# Docking_Connection.net
KiCad netlist of a schematic drawn in Altium Designer
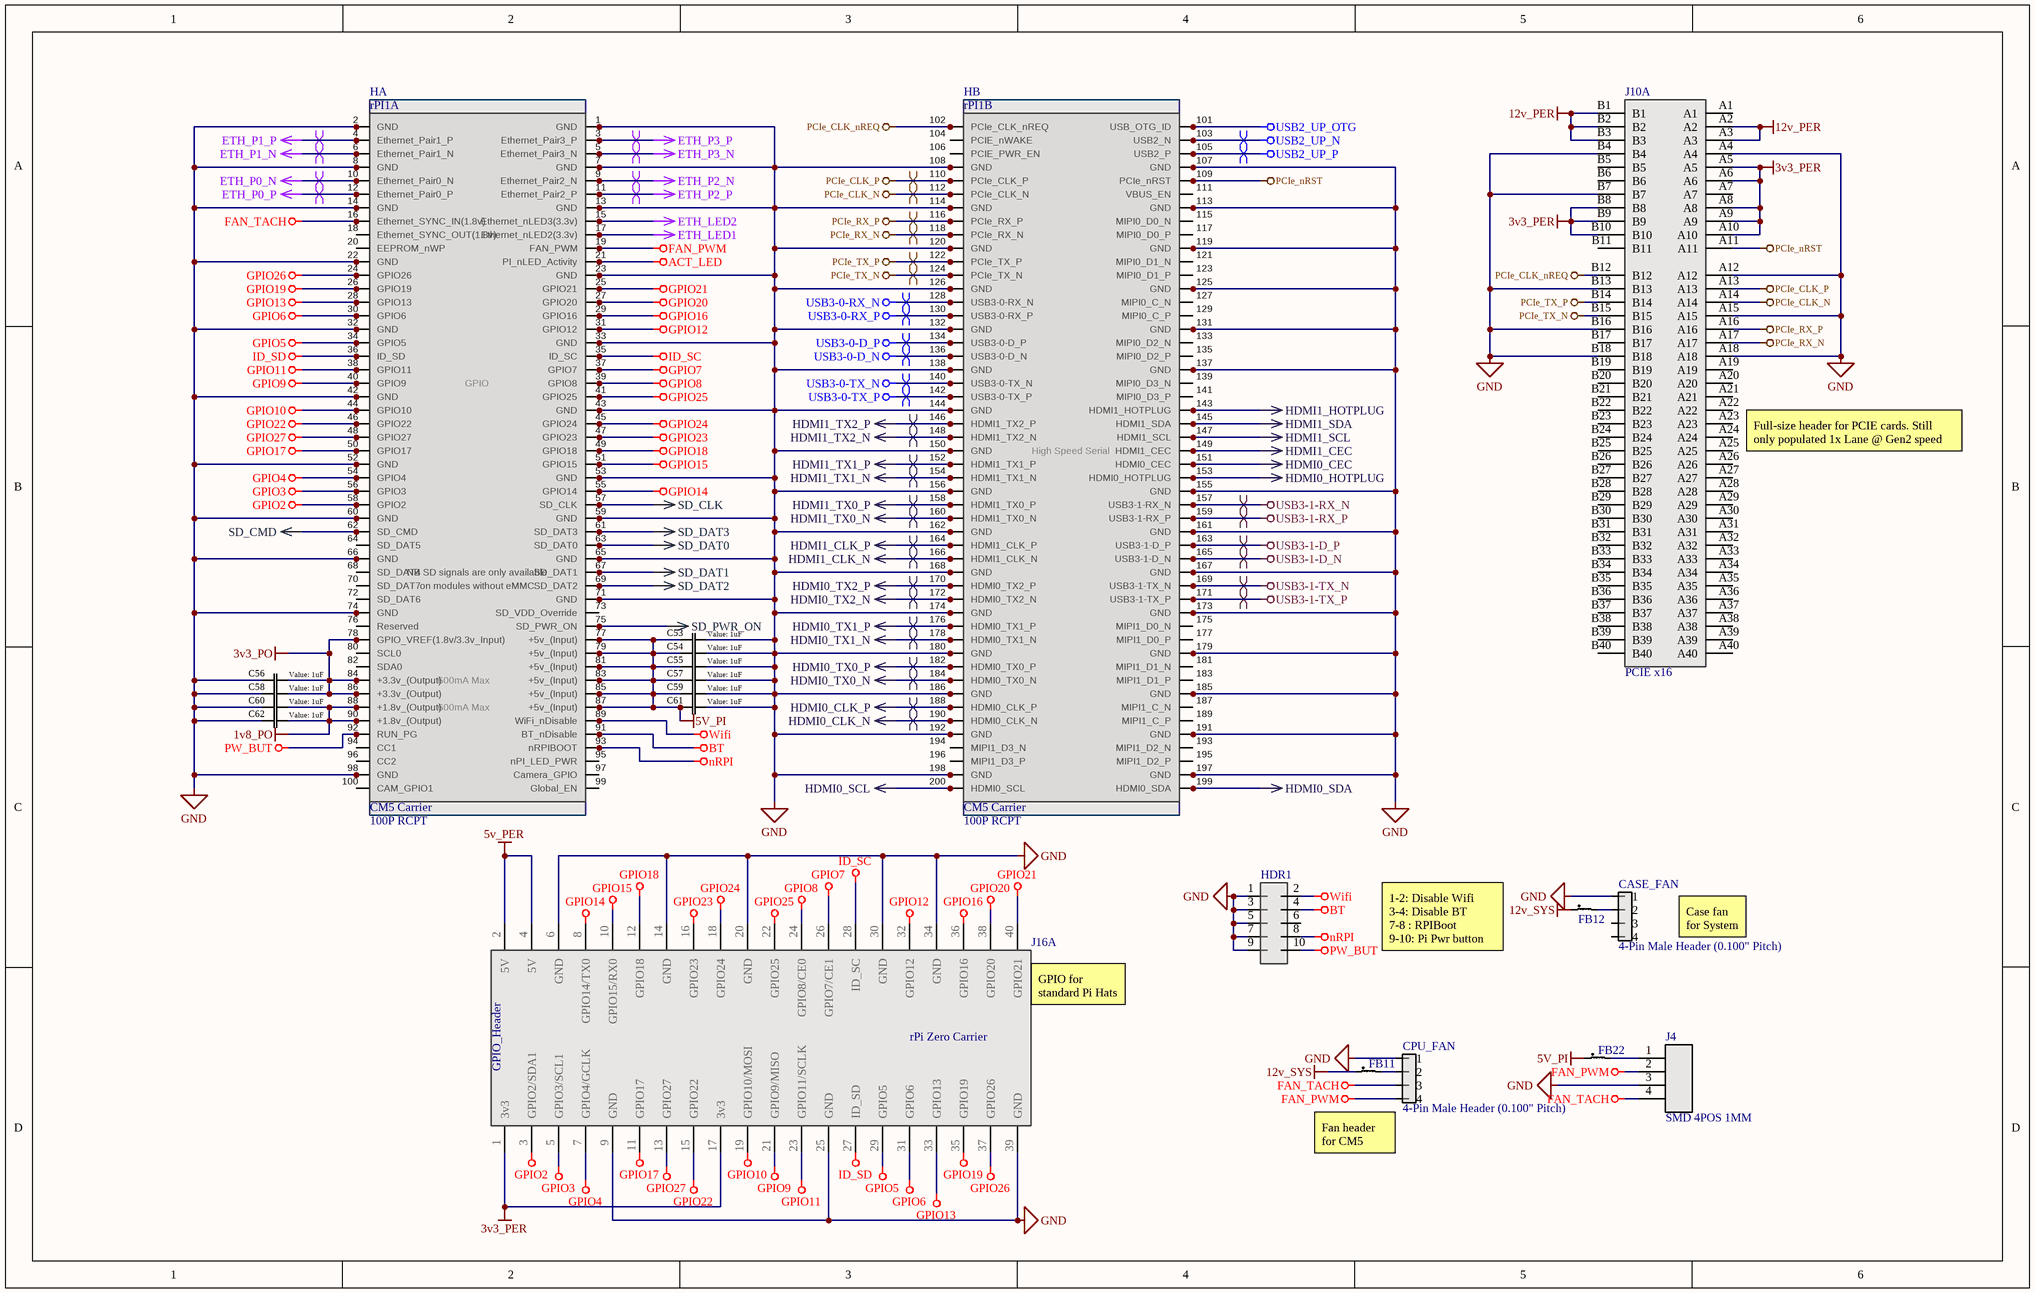
[diagram p0: Docking_Connection.SchDoc]

(export (version "E")
  (design (tool "Eeschema 10.0.6"))
  (components
    (comp (ref "C53")
      (value "1uF")
      (footprint "0603")
      (fields
        (field (name "VOLTAGE") "6V")
        (field (name "TOLERANCE") "5%")
        (field (name "Comment") "Generic Capacitor")
      )
      (libsource (lib "Capacitors") (part "Generic Capacitor"))
    )
    (comp (ref "C54")
      (value "1uF")
      (footprint "0603")
      (fields
        (field (name "VOLTAGE") "6V")
        (field (name "TOLERANCE") "5%")
        (field (name "Comment") "Generic Capacitor")
      )
      (libsource (lib "Capacitors") (part "Generic Capacitor"))
    )
    (comp (ref "C55")
      (value "1uF")
      (footprint "0603")
      (fields
        (field (name "VOLTAGE") "6V")
        (field (name "TOLERANCE") "5%")
        (field (name "Comment") "Generic Capacitor")
      )
      (libsource (lib "Capacitors") (part "Generic Capacitor"))
    )
    (comp (ref "C56")
      (value "1uF")
      (footprint "0603")
      (fields
        (field (name "VOLTAGE") "6V")
        (field (name "TOLERANCE") "5%")
        (field (name "Comment") "Generic Capacitor")
      )
      (libsource (lib "Capacitors") (part "Generic Capacitor"))
    )
    (comp (ref "C57")
      (value "1uF")
      (footprint "0603")
      (fields
        (field (name "VOLTAGE") "6V")
        (field (name "TOLERANCE") "5%")
        (field (name "Comment") "Generic Capacitor")
      )
      (libsource (lib "Capacitors") (part "Generic Capacitor"))
    )
    (comp (ref "C58")
      (value "1uF")
      (footprint "0603")
      (fields
        (field (name "VOLTAGE") "6V")
        (field (name "TOLERANCE") "5%")
        (field (name "Comment") "Generic Capacitor")
      )
      (libsource (lib "Capacitors") (part "Generic Capacitor"))
    )
    (comp (ref "C59")
      (value "1uF")
      (footprint "0603")
      (fields
        (field (name "VOLTAGE") "6V")
        (field (name "TOLERANCE") "5%")
        (field (name "Comment") "Generic Capacitor")
      )
      (libsource (lib "Capacitors") (part "Generic Capacitor"))
    )
    (comp (ref "C60")
      (value "1uF")
      (footprint "0603")
      (fields
        (field (name "VOLTAGE") "6V")
        (field (name "TOLERANCE") "5%")
        (field (name "Comment") "Generic Capacitor")
      )
      (libsource (lib "Capacitors") (part "Generic Capacitor"))
    )
    (comp (ref "C61")
      (value "1uF")
      (footprint "0603")
      (fields
        (field (name "VOLTAGE") "6V")
        (field (name "TOLERANCE") "5%")
        (field (name "Comment") "Generic Capacitor")
      )
      (libsource (lib "Capacitors") (part "Generic Capacitor"))
    )
    (comp (ref "C62")
      (value "1uF")
      (footprint "0603")
      (fields
        (field (name "VOLTAGE") "6V")
        (field (name "TOLERANCE") "5%")
        (field (name "Comment") "Generic Capacitor")
      )
      (libsource (lib "Capacitors") (part "Generic Capacitor"))
    )
    (comp (ref "CASE_FAN")
      (value "4-Pin Male Header (0.100\" Pitch)")
      (footprint "TSW-104-07-T-S")
      (description "Connector Header Through Hole 4 position 0.100\" (2.54mm)")
      (libsource (lib "Connectors") (part "TSW-104-07-T-S"))
    )
    (comp (ref "CPU_FAN")
      (value "4-Pin Male Header (0.100\" Pitch)")
      (footprint "TSW-104-07-T-S")
      (description "Connector Header Through Hole 4 position 0.100\" (2.54mm)")
      (libsource (lib "Connectors") (part "TSW-104-07-T-S"))
    )
    (comp (ref "FB11")
      (value "0603 Ferrite")
      (footprint "0603")
      (description "120 Ohms @ 100 MHz 1 Signal Line Ferrite Bead 0603 (1608 Metric) 500mA 180mOhm")
      (fields
        (field (name "MANUFACTURER") "Pulse")
        (field (name "MANUFACTURER PART NUMBER") "PE-0603FB121ST")
      )
      (libsource (lib "Inductors") (part "PE-0603FB121ST"))
    )
    (comp (ref "FB12")
      (value "0603 Ferrite")
      (footprint "0603")
      (description "120 Ohms @ 100 MHz 1 Signal Line Ferrite Bead 0603 (1608 Metric) 500mA 180mOhm")
      (fields
        (field (name "MANUFACTURER") "Pulse")
        (field (name "MANUFACTURER PART NUMBER") "PE-0603FB121ST")
      )
      (libsource (lib "Inductors") (part "PE-0603FB121ST"))
    )
    (comp (ref "FB22")
      (value "0603 Ferrite")
      (footprint "0603")
      (description "120 Ohms @ 100 MHz 1 Signal Line Ferrite Bead 0603 (1608 Metric) 500mA 180mOhm")
      (fields
        (field (name "MANUFACTURER") "Pulse")
        (field (name "MANUFACTURER PART NUMBER") "PE-0603FB121ST")
      )
      (libsource (lib "Inductors") (part "PE-0603FB121ST"))
    )
    (comp (ref "HA")
      (value "100P RCPT")
      (footprint "DF40HC(3.0)-100DS-0.4V(51)")
      (description "100 Position Connector Receptacle, Center Strip Contacts Surface Mount Gold")
      (fields (field (name "MF") "Hirose") (field (name "MP") "DF40C-100DS-0.4V(51)"))
      (libsource (lib "Connectors") (part "DF40-100DS RCPT_1"))
    )
    (comp (ref "HB")
      (value "100P RCPT")
      (footprint "DF40HC(3.0)-100DS-0.4V(51)")
      (description "100 Position Connector Receptacle, Center Strip Contacts Surface Mount Gold")
      (fields (field (name "MF") "Hirose") (field (name "MP") "DF40C-100DS-0.4V(51)"))
      (libsource (lib "Connectors") (part "DF40-100DS RCPT_1"))
    )
    (comp (ref "HDR1")
      (value "10pinMobo")
      (footprint "10pinMobo")
      (description "10pin motherboard jack")
      (libsource (lib "Connectors") (part "10pinMobo"))
    )
    (comp (ref "J4")
      (value "SMD 4POS 1MM")
      (footprint "CONN4_BM04B-SRSS_JST")
      (description "Connector Header Surface Mount 4 position 0.039\" (1.00mm)")
      (libsource (lib "Connectors") (part "BM04B-SRSS-TB"))
    )
    (comp (ref "J10")
      (value "PCIE x16")
      (footprint "10018783-10203TLF")
      (description "164 Position Female Connector PCI Express™ Gold 0.039\" (1.00mm) Black")
      (fields (field (name "MF") "Amphenol ICC") (field (name "MP") "10018783-10203TLF"))
      (libsource (lib "Connectors") (part "10018783-10203TLF"))
    )
    (comp (ref "J16")
      (value "rPi Zero Carrier")
      (footprint "rPiZero")
      (description "Raspberry Pi Zero/W/2W\r\nHeader, debug-pads, & mounting")
      (libsource (lib "SOC_Carrier") (part "RP-Zero"))
    )
    (comp (ref "rPI1")
      (value "CM5 Carrier")
      (footprint "CM4-FTPD")
      (description "Compute Module 5 Footprint\r\nOverlap Hirose 100P connector over pads to place actual components")
      (libsource (lib "Misc ICs") (part "RP-CM5"))
    )
  )
  (nets
    (net (code "1") (name "1v8_PO") (class "Default")
      (node (ref "C60") (pin "1") (pinfunction "1_1") (pintype "passive"))
      (node (ref "C62") (pin "1") (pinfunction "1_1") (pintype "passive"))
      (node (ref "HA") (pin "88") (pinfunction "88_88") (pintype "passive"))
      (node (ref "HA") (pin "90") (pinfunction "90_90") (pintype "passive"))
      (node (ref "rPI1") (pin "88") (pinfunction "+1.8v_(Output)_88") (pintype "passive"))
      (node (ref "rPI1") (pin "90") (pinfunction "+1.8v_(Output)_90") (pintype "passive"))
    )
    (net (code "2") (name "3v3_PER") (class "Default")
      (node (ref "J10") (pin "A10") (pinfunction "A10_A10") (pintype "passive"))
      (node (ref "J10") (pin "A5") (pinfunction "A5_A5") (pintype "passive"))
      (node (ref "J10") (pin "A6") (pinfunction "A6_A6") (pintype "passive"))
      (node (ref "J10") (pin "A8") (pinfunction "A8_A8") (pintype "passive"))
      (node (ref "J10") (pin "A9") (pinfunction "A9_A9") (pintype "passive"))
      (node (ref "J10") (pin "B10") (pinfunction "B10_B10") (pintype "passive"))
      (node (ref "J10") (pin "B8") (pinfunction "B8_B8") (pintype "passive"))
      (node (ref "J10") (pin "B9") (pinfunction "B9_B9") (pintype "passive"))
      (node (ref "J16") (pin "1") (pinfunction "3v3_1") (pintype "passive"))
      (node (ref "J16") (pin "17") (pinfunction "3v3_17") (pintype "passive"))
    )
    (net (code "3") (name "3v3_PO") (class "Default")
      (node (ref "C56") (pin "1") (pinfunction "1_1") (pintype "passive"))
      (node (ref "C58") (pin "1") (pinfunction "1_1") (pintype "passive"))
      (node (ref "HA") (pin "78") (pinfunction "78_78") (pintype "passive"))
      (node (ref "HA") (pin "84") (pinfunction "84_84") (pintype "passive"))
      (node (ref "HA") (pin "86") (pinfunction "86_86") (pintype "passive"))
      (node (ref "rPI1") (pin "78") (pinfunction "GPIO_VREF(1.8v/3.3v_Input)_78") (pintype "passive"))
      (node (ref "rPI1") (pin "84") (pinfunction "+3.3v_(Output)_84") (pintype "passive"))
      (node (ref "rPI1") (pin "86") (pinfunction "+3.3v_(Output)_86") (pintype "passive"))
    )
    (net (code "4") (name "5V_PI") (class "Default")
      (node (ref "C53") (pin "2") (pinfunction "2_2") (pintype "passive"))
      (node (ref "C54") (pin "2") (pinfunction "2_2") (pintype "passive"))
      (node (ref "C55") (pin "2") (pinfunction "2_2") (pintype "passive"))
      (node (ref "C57") (pin "2") (pinfunction "2_2") (pintype "passive"))
      (node (ref "C59") (pin "2") (pinfunction "2_2") (pintype "passive"))
      (node (ref "C61") (pin "2") (pinfunction "2_2") (pintype "passive"))
      (node (ref "FB22") (pin "1") (pinfunction "1_1") (pintype "passive"))
      (node (ref "HA") (pin "77") (pinfunction "77_77") (pintype "passive"))
      (node (ref "HA") (pin "79") (pinfunction "79_79") (pintype "passive"))
      (node (ref "HA") (pin "81") (pinfunction "81_81") (pintype "passive"))
      (node (ref "HA") (pin "83") (pinfunction "83_83") (pintype "passive"))
      (node (ref "HA") (pin "85") (pinfunction "85_85") (pintype "passive"))
      (node (ref "HA") (pin "87") (pinfunction "87_87") (pintype "passive"))
      (node (ref "rPI1") (pin "77") (pinfunction "+5v_(Input)_77") (pintype "passive"))
      (node (ref "rPI1") (pin "79") (pinfunction "+5v_(Input)_79") (pintype "passive"))
      (node (ref "rPI1") (pin "81") (pinfunction "+5v_(Input)_81") (pintype "passive"))
      (node (ref "rPI1") (pin "83") (pinfunction "+5v_(Input)_83") (pintype "passive"))
      (node (ref "rPI1") (pin "85") (pinfunction "+5v_(Input)_85") (pintype "passive"))
      (node (ref "rPI1") (pin "87") (pinfunction "+5v_(Input)_87") (pintype "passive"))
    )
    (net (code "5") (name "5v_PER") (class "Default")
      (node (ref "J16") (pin "2") (pinfunction "5V_2") (pintype "passive"))
      (node (ref "J16") (pin "4") (pinfunction "5V_4") (pintype "passive"))
    )
    (net (code "6") (name "12v_PER") (class "Default")
      (node (ref "J10") (pin "A2") (pinfunction "A2_A2") (pintype "passive"))
      (node (ref "J10") (pin "A3") (pinfunction "A3_A3") (pintype "passive"))
      (node (ref "J10") (pin "B1") (pinfunction "B1_B1") (pintype "passive"))
      (node (ref "J10") (pin "B2") (pinfunction "B2_B2") (pintype "passive"))
      (node (ref "J10") (pin "B3") (pinfunction "B3_B3") (pintype "passive"))
    )
    (net (code "7") (name "12v_SYS") (class "Default")
      (node (ref "FB11") (pin "1") (pinfunction "1_1") (pintype "passive"))
      (node (ref "FB12") (pin "1") (pinfunction "1_1") (pintype "passive"))
    )
    (net (code "8") (name "ACT_LED") (class "Default")
      (node (ref "HA") (pin "21") (pinfunction "21_21") (pintype "passive"))
      (node (ref "rPI1") (pin "21") (pinfunction "PI_nLED_Activity_21") (pintype "passive"))
    )
    (net (code "9") (name "BT") (class "Default")
      (node (ref "HA") (pin "91") (pinfunction "91_91") (pintype "passive"))
      (node (ref "HDR1") (pin "4") (pinfunction "4_4") (pintype "passive"))
      (node (ref "rPI1") (pin "91") (pinfunction "BT_nDisable_91") (pintype "passive"))
    )
    (net (code "10") (name "ETH_LED1") (class "Default")
      (node (ref "HA") (pin "17") (pinfunction "17_17") (pintype "passive"))
      (node (ref "rPI1") (pin "17") (pinfunction "Ethernet_nLED2(3.3v)_17") (pintype "passive"))
    )
    (net (code "11") (name "ETH_LED2") (class "Default")
      (node (ref "HA") (pin "15") (pinfunction "15_15") (pintype "passive"))
      (node (ref "rPI1") (pin "15") (pinfunction "Ethernet_nLED3(3.3v)_15") (pintype "passive"))
    )
    (net (code "12") (name "ETH_P0_N") (class "Default")
      (node (ref "HA") (pin "10") (pinfunction "10_10") (pintype "passive"))
      (node (ref "rPI1") (pin "10") (pinfunction "Ethernet_Pair0_N_10") (pintype "passive"))
    )
    (net (code "13") (name "ETH_P0_P") (class "Default")
      (node (ref "HA") (pin "12") (pinfunction "12_12") (pintype "passive"))
      (node (ref "rPI1") (pin "12") (pinfunction "Ethernet_Pair0_P_12") (pintype "passive"))
    )
    (net (code "14") (name "ETH_P1_N") (class "Default")
      (node (ref "HA") (pin "6") (pinfunction "6_6") (pintype "passive"))
      (node (ref "rPI1") (pin "6") (pinfunction "Ethernet_Pair1_N_6") (pintype "passive"))
    )
    (net (code "15") (name "ETH_P1_P") (class "Default")
      (node (ref "HA") (pin "4") (pinfunction "4_4") (pintype "passive"))
      (node (ref "rPI1") (pin "4") (pinfunction "Ethernet_Pair1_P_4") (pintype "passive"))
    )
    (net (code "16") (name "ETH_P2_N") (class "Default")
      (node (ref "HA") (pin "9") (pinfunction "9_9") (pintype "passive"))
      (node (ref "rPI1") (pin "9") (pinfunction "Ethernet_Pair2_N_9") (pintype "passive"))
    )
    (net (code "17") (name "ETH_P2_P") (class "Default")
      (node (ref "HA") (pin "11") (pinfunction "11_11") (pintype "passive"))
      (node (ref "rPI1") (pin "11") (pinfunction "Ethernet_Pair2_P_11") (pintype "passive"))
    )
    (net (code "18") (name "ETH_P3_N") (class "Default")
      (node (ref "HA") (pin "5") (pinfunction "5_5") (pintype "passive"))
      (node (ref "rPI1") (pin "5") (pinfunction "Ethernet_Pair3_N_5") (pintype "passive"))
    )
    (net (code "19") (name "ETH_P3_P") (class "Default")
      (node (ref "HA") (pin "3") (pinfunction "3_3") (pintype "passive"))
      (node (ref "rPI1") (pin "3") (pinfunction "Ethernet_Pair3_P_3") (pintype "passive"))
    )
    (net (code "20") (name "FAN_PWM") (class "Default")
      (node (ref "CPU_FAN") (pin "4") (pinfunction "4_4") (pintype "passive"))
      (node (ref "HA") (pin "19") (pinfunction "19_19") (pintype "passive"))
      (node (ref "J4") (pin "2") (pinfunction "2_2") (pintype "passive"))
      (node (ref "rPI1") (pin "19") (pinfunction "FAN_PWM_19") (pintype "passive"))
    )
    (net (code "21") (name "FAN_TACH") (class "Default")
      (node (ref "CPU_FAN") (pin "3") (pinfunction "3_3") (pintype "passive"))
      (node (ref "HA") (pin "16") (pinfunction "16_16") (pintype "passive"))
      (node (ref "J4") (pin "4") (pinfunction "4_4") (pintype "passive"))
      (node (ref "rPI1") (pin "16") (pinfunction "Ethernet_SYNC_IN(1.8v)_16") (pintype "passive"))
    )
    (net (code "22") (name "GND") (class "Default")
      (node (ref "C53") (pin "1") (pinfunction "1_1") (pintype "passive"))
      (node (ref "C54") (pin "1") (pinfunction "1_1") (pintype "passive"))
      (node (ref "C55") (pin "1") (pinfunction "1_1") (pintype "passive"))
      (node (ref "C56") (pin "2") (pinfunction "2_2") (pintype "passive"))
      (node (ref "C57") (pin "1") (pinfunction "1_1") (pintype "passive"))
      (node (ref "C58") (pin "2") (pinfunction "2_2") (pintype "passive"))
      (node (ref "C59") (pin "1") (pinfunction "1_1") (pintype "passive"))
      (node (ref "C60") (pin "2") (pinfunction "2_2") (pintype "passive"))
      (node (ref "C61") (pin "1") (pinfunction "1_1") (pintype "passive"))
      (node (ref "C62") (pin "2") (pinfunction "2_2") (pintype "passive"))
      (node (ref "CASE_FAN") (pin "1") (pinfunction "1_1") (pintype "passive"))
      (node (ref "CPU_FAN") (pin "1") (pinfunction "1_1") (pintype "passive"))
      (node (ref "HA") (pin "1") (pinfunction "1_1") (pintype "passive"))
      (node (ref "HA") (pin "13") (pinfunction "13_13") (pintype "passive"))
      (node (ref "HA") (pin "14") (pinfunction "14_14") (pintype "passive"))
      (node (ref "HA") (pin "2") (pinfunction "2_2") (pintype "passive"))
      (node (ref "HA") (pin "22") (pinfunction "22_22") (pintype "passive"))
      (node (ref "HA") (pin "23") (pinfunction "23_23") (pintype "passive"))
      (node (ref "HA") (pin "32") (pinfunction "32_32") (pintype "passive"))
      (node (ref "HA") (pin "33") (pinfunction "33_33") (pintype "passive"))
      (node (ref "HA") (pin "42") (pinfunction "42_42") (pintype "passive"))
      (node (ref "HA") (pin "43") (pinfunction "43_43") (pintype "passive"))
      (node (ref "HA") (pin "52") (pinfunction "52_52") (pintype "passive"))
      (node (ref "HA") (pin "53") (pinfunction "53_53") (pintype "passive"))
      (node (ref "HA") (pin "59") (pinfunction "59_59") (pintype "passive"))
      (node (ref "HA") (pin "60") (pinfunction "60_60") (pintype "passive"))
      (node (ref "HA") (pin "65") (pinfunction "65_65") (pintype "passive"))
      (node (ref "HA") (pin "66") (pinfunction "66_66") (pintype "passive"))
      (node (ref "HA") (pin "7") (pinfunction "7_7") (pintype "passive"))
      (node (ref "HA") (pin "71") (pinfunction "71_71") (pintype "passive"))
      (node (ref "HA") (pin "74") (pinfunction "74_74") (pintype "passive"))
      (node (ref "HA") (pin "8") (pinfunction "8_8") (pintype "passive"))
      (node (ref "HA") (pin "98") (pinfunction "98_98") (pintype "passive"))
      (node (ref "HB") (pin "13") (pinfunction "13_13") (pintype "passive"))
      (node (ref "HB") (pin "14") (pinfunction "14_14") (pintype "passive"))
      (node (ref "HB") (pin "19") (pinfunction "19_19") (pintype "passive"))
      (node (ref "HB") (pin "20") (pinfunction "20_20") (pintype "passive"))
      (node (ref "HB") (pin "25") (pinfunction "25_25") (pintype "passive"))
      (node (ref "HB") (pin "26") (pinfunction "26_26") (pintype "passive"))
      (node (ref "HB") (pin "31") (pinfunction "31_31") (pintype "passive"))
      (node (ref "HB") (pin "32") (pinfunction "32_32") (pintype "passive"))
      (node (ref "HB") (pin "37") (pinfunction "37_37") (pintype "passive"))
      (node (ref "HB") (pin "38") (pinfunction "38_38") (pintype "passive"))
      (node (ref "HB") (pin "44") (pinfunction "44_44") (pintype "passive"))
      (node (ref "HB") (pin "50") (pinfunction "50_50") (pintype "passive"))
      (node (ref "HB") (pin "55") (pinfunction "55_55") (pintype "passive"))
      (node (ref "HB") (pin "56") (pinfunction "56_56") (pintype "passive"))
      (node (ref "HB") (pin "61") (pinfunction "61_61") (pintype "passive"))
      (node (ref "HB") (pin "62") (pinfunction "62_62") (pintype "passive"))
      (node (ref "HB") (pin "67") (pinfunction "67_67") (pintype "passive"))
      (node (ref "HB") (pin "68") (pinfunction "68_68") (pintype "passive"))
      (node (ref "HB") (pin "7") (pinfunction "7_7") (pintype "passive"))
      (node (ref "HB") (pin "73") (pinfunction "73_73") (pintype "passive"))
      (node (ref "HB") (pin "74") (pinfunction "74_74") (pintype "passive"))
      (node (ref "HB") (pin "79") (pinfunction "79_79") (pintype "passive"))
      (node (ref "HB") (pin "8") (pinfunction "8_8") (pintype "passive"))
      (node (ref "HB") (pin "80") (pinfunction "80_80") (pintype "passive"))
      (node (ref "HB") (pin "85") (pinfunction "85_85") (pintype "passive"))
      (node (ref "HB") (pin "86") (pinfunction "86_86") (pintype "passive"))
      (node (ref "HB") (pin "91") (pinfunction "91_91") (pintype "passive"))
      (node (ref "HB") (pin "92") (pinfunction "92_92") (pintype "passive"))
      (node (ref "HB") (pin "97") (pinfunction "97_97") (pintype "passive"))
      (node (ref "HB") (pin "98") (pinfunction "98_98") (pintype "passive"))
      (node (ref "HDR1") (pin "1") (pinfunction "1_1") (pintype "passive"))
      (node (ref "HDR1") (pin "3") (pinfunction "3_3") (pintype "passive"))
      (node (ref "HDR1") (pin "5") (pinfunction "5_5") (pintype "passive"))
      (node (ref "HDR1") (pin "7") (pinfunction "7_7") (pintype "passive"))
      (node (ref "HDR1") (pin "9") (pinfunction "9_9") (pintype "passive"))
      (node (ref "J10") (pin "A12") (pinfunction "A12_A12") (pintype "passive"))
      (node (ref "J10") (pin "A15") (pinfunction "A15_A15") (pintype "passive"))
      (node (ref "J10") (pin "A18") (pinfunction "A18_A18") (pintype "passive"))
      (node (ref "J10") (pin "A4") (pinfunction "A4_A4") (pintype "passive"))
      (node (ref "J10") (pin "B13") (pinfunction "B13_B13") (pintype "passive"))
      (node (ref "J10") (pin "B16") (pinfunction "B16_B16") (pintype "passive"))
      (node (ref "J10") (pin "B18") (pinfunction "B18_B18") (pintype "passive"))
      (node (ref "J10") (pin "B4") (pinfunction "B4_B4") (pintype "passive"))
      (node (ref "J10") (pin "B7") (pinfunction "B7_B7") (pintype "passive"))
      (node (ref "J16") (pin "14") (pinfunction "GND_14") (pintype "passive"))
      (node (ref "J16") (pin "20") (pinfunction "GND_20") (pintype "passive"))
      (node (ref "J16") (pin "25") (pinfunction "GND_25") (pintype "passive"))
      (node (ref "J16") (pin "30") (pinfunction "GND_30") (pintype "passive"))
      (node (ref "J16") (pin "34") (pinfunction "GND_34") (pintype "passive"))
      (node (ref "J16") (pin "39") (pinfunction "GND_39") (pintype "passive"))
      (node (ref "J16") (pin "6") (pinfunction "GND_6") (pintype "passive"))
      (node (ref "J16") (pin "9") (pinfunction "GND_9") (pintype "passive"))
      (node (ref "J4") (pin "3") (pinfunction "3_3") (pintype "passive"))
      (node (ref "rPI1") (pin "1") (pinfunction "GND_1") (pintype "passive"))
      (node (ref "rPI1") (pin "107") (pinfunction "GND_107") (pintype "passive"))
      (node (ref "rPI1") (pin "108") (pinfunction "GND_108") (pintype "passive"))
      (node (ref "rPI1") (pin "113") (pinfunction "GND_113") (pintype "passive"))
      (node (ref "rPI1") (pin "114") (pinfunction "GND_114") (pintype "passive"))
      (node (ref "rPI1") (pin "119") (pinfunction "GND_119") (pintype "passive"))
      (node (ref "rPI1") (pin "120") (pinfunction "GND_120") (pintype "passive"))
      (node (ref "rPI1") (pin "125") (pinfunction "GND_125") (pintype "passive"))
      (node (ref "rPI1") (pin "126") (pinfunction "GND_126") (pintype "passive"))
      (node (ref "rPI1") (pin "13") (pinfunction "GND_13") (pintype "passive"))
      (node (ref "rPI1") (pin "131") (pinfunction "GND_131") (pintype "passive"))
      (node (ref "rPI1") (pin "132") (pinfunction "GND_132") (pintype "passive"))
      (node (ref "rPI1") (pin "137") (pinfunction "GND_137") (pintype "passive"))
      (node (ref "rPI1") (pin "138") (pinfunction "GND_138") (pintype "passive"))
      (node (ref "rPI1") (pin "14") (pinfunction "GND_14") (pintype "passive"))
      (node (ref "rPI1") (pin "144") (pinfunction "GND_144") (pintype "passive"))
      (node (ref "rPI1") (pin "150") (pinfunction "GND_150") (pintype "passive"))
      (node (ref "rPI1") (pin "155") (pinfunction "GND_155") (pintype "passive"))
      (node (ref "rPI1") (pin "156") (pinfunction "GND_156") (pintype "passive"))
      (node (ref "rPI1") (pin "161") (pinfunction "GND_161") (pintype "passive"))
      (node (ref "rPI1") (pin "162") (pinfunction "GND_162") (pintype "passive"))
      (node (ref "rPI1") (pin "167") (pinfunction "GND_167") (pintype "passive"))
      (node (ref "rPI1") (pin "168") (pinfunction "GND_168") (pintype "passive"))
      (node (ref "rPI1") (pin "173") (pinfunction "GND_173") (pintype "passive"))
      (node (ref "rPI1") (pin "174") (pinfunction "GND_174") (pintype "passive"))
      (node (ref "rPI1") (pin "179") (pinfunction "GND_179") (pintype "passive"))
      (node (ref "rPI1") (pin "180") (pinfunction "GND_180") (pintype "passive"))
      (node (ref "rPI1") (pin "185") (pinfunction "GND_185") (pintype "passive"))
      (node (ref "rPI1") (pin "186") (pinfunction "GND_186") (pintype "passive"))
      (node (ref "rPI1") (pin "191") (pinfunction "GND_191") (pintype "passive"))
      (node (ref "rPI1") (pin "192") (pinfunction "GND_192") (pintype "passive"))
      (node (ref "rPI1") (pin "197") (pinfunction "GND_197") (pintype "passive"))
      (node (ref "rPI1") (pin "198") (pinfunction "GND_198") (pintype "passive"))
      (node (ref "rPI1") (pin "2") (pinfunction "GND_2") (pintype "passive"))
      (node (ref "rPI1") (pin "22") (pinfunction "GND_22") (pintype "passive"))
      (node (ref "rPI1") (pin "23") (pinfunction "GND_23") (pintype "passive"))
      (node (ref "rPI1") (pin "32") (pinfunction "GND_32") (pintype "passive"))
      (node (ref "rPI1") (pin "33") (pinfunction "GND_33") (pintype "passive"))
      (node (ref "rPI1") (pin "42") (pinfunction "GND_42") (pintype "passive"))
      (node (ref "rPI1") (pin "43") (pinfunction "GND_43") (pintype "passive"))
      (node (ref "rPI1") (pin "52") (pinfunction "GND_52") (pintype "passive"))
      (node (ref "rPI1") (pin "53") (pinfunction "GND_53") (pintype "passive"))
      (node (ref "rPI1") (pin "59") (pinfunction "GND_59") (pintype "passive"))
      (node (ref "rPI1") (pin "60") (pinfunction "GND_60") (pintype "passive"))
      (node (ref "rPI1") (pin "65") (pinfunction "GND_65") (pintype "passive"))
      (node (ref "rPI1") (pin "66") (pinfunction "GND_66") (pintype "passive"))
      (node (ref "rPI1") (pin "7") (pinfunction "GND_7") (pintype "passive"))
      (node (ref "rPI1") (pin "71") (pinfunction "GND_71") (pintype "passive"))
      (node (ref "rPI1") (pin "74") (pinfunction "GND_74") (pintype "passive"))
      (node (ref "rPI1") (pin "8") (pinfunction "GND_8") (pintype "passive"))
      (node (ref "rPI1") (pin "98") (pinfunction "GND_98") (pintype "passive"))
    )
    (net (code "23") (name "GPIO2") (class "Default")
      (node (ref "HA") (pin "58") (pinfunction "58_58") (pintype "passive"))
      (node (ref "J16") (pin "3") (pinfunction "GPIO2/SDA1_3") (pintype "passive"))
      (node (ref "rPI1") (pin "58") (pinfunction "GPIO2_58") (pintype "passive"))
    )
    (net (code "24") (name "GPIO3") (class "Default")
      (node (ref "HA") (pin "56") (pinfunction "56_56") (pintype "passive"))
      (node (ref "J16") (pin "5") (pinfunction "GPIO3/SCL1_5") (pintype "passive"))
      (node (ref "rPI1") (pin "56") (pinfunction "GPIO3_56") (pintype "passive"))
    )
    (net (code "25") (name "GPIO4") (class "Default")
      (node (ref "HA") (pin "54") (pinfunction "54_54") (pintype "passive"))
      (node (ref "J16") (pin "7") (pinfunction "GPIO4/GCLK_7") (pintype "passive"))
      (node (ref "rPI1") (pin "54") (pinfunction "GPIO4_54") (pintype "passive"))
    )
    (net (code "26") (name "GPIO5") (class "Default")
      (node (ref "HA") (pin "34") (pinfunction "34_34") (pintype "passive"))
      (node (ref "J16") (pin "29") (pinfunction "GPIO5_29") (pintype "passive"))
      (node (ref "rPI1") (pin "34") (pinfunction "GPIO5_34") (pintype "passive"))
    )
    (net (code "27") (name "GPIO6") (class "Default")
      (node (ref "HA") (pin "30") (pinfunction "30_30") (pintype "passive"))
      (node (ref "J16") (pin "31") (pinfunction "GPIO6_31") (pintype "passive"))
      (node (ref "rPI1") (pin "30") (pinfunction "GPIO6_30") (pintype "passive"))
    )
    (net (code "28") (name "GPIO7") (class "Default")
      (node (ref "HA") (pin "37") (pinfunction "37_37") (pintype "passive"))
      (node (ref "J16") (pin "26") (pinfunction "GPIO7/CE1_26") (pintype "passive"))
      (node (ref "rPI1") (pin "37") (pinfunction "GPIO7_37") (pintype "passive"))
    )
    (net (code "29") (name "GPIO8") (class "Default")
      (node (ref "HA") (pin "39") (pinfunction "39_39") (pintype "passive"))
      (node (ref "J16") (pin "24") (pinfunction "GPIO8/CE0_24") (pintype "passive"))
      (node (ref "rPI1") (pin "39") (pinfunction "GPIO8_39") (pintype "passive"))
    )
    (net (code "30") (name "GPIO9") (class "Default")
      (node (ref "HA") (pin "40") (pinfunction "40_40") (pintype "passive"))
      (node (ref "J16") (pin "21") (pinfunction "GPIO9/MISO_21") (pintype "passive"))
      (node (ref "rPI1") (pin "40") (pinfunction "GPIO9_40") (pintype "passive"))
    )
    (net (code "31") (name "GPIO10") (class "Default")
      (node (ref "HA") (pin "44") (pinfunction "44_44") (pintype "passive"))
      (node (ref "J16") (pin "19") (pinfunction "GPIO10/MOSI_19") (pintype "passive"))
      (node (ref "rPI1") (pin "44") (pinfunction "GPIO10_44") (pintype "passive"))
    )
    (net (code "32") (name "GPIO11") (class "Default")
      (node (ref "HA") (pin "38") (pinfunction "38_38") (pintype "passive"))
      (node (ref "J16") (pin "23") (pinfunction "GPIO11/SCLK_23") (pintype "passive"))
      (node (ref "rPI1") (pin "38") (pinfunction "GPIO11_38") (pintype "passive"))
    )
    (net (code "33") (name "GPIO12") (class "Default")
      (node (ref "HA") (pin "31") (pinfunction "31_31") (pintype "passive"))
      (node (ref "J16") (pin "32") (pinfunction "GPIO12_32") (pintype "passive"))
      (node (ref "rPI1") (pin "31") (pinfunction "GPIO12_31") (pintype "passive"))
    )
    (net (code "34") (name "GPIO13") (class "Default")
      (node (ref "HA") (pin "28") (pinfunction "28_28") (pintype "passive"))
      (node (ref "J16") (pin "33") (pinfunction "GPIO13_33") (pintype "passive"))
      (node (ref "rPI1") (pin "28") (pinfunction "GPIO13_28") (pintype "passive"))
    )
    (net (code "35") (name "GPIO14") (class "Default")
      (node (ref "HA") (pin "55") (pinfunction "55_55") (pintype "passive"))
      (node (ref "J16") (pin "8") (pinfunction "GPIO14/TX0_8") (pintype "passive"))
      (node (ref "rPI1") (pin "55") (pinfunction "GPIO14_55") (pintype "passive"))
    )
    (net (code "36") (name "GPIO15") (class "Default")
      (node (ref "HA") (pin "51") (pinfunction "51_51") (pintype "passive"))
      (node (ref "J16") (pin "10") (pinfunction "GPIO15/RX0_10") (pintype "passive"))
      (node (ref "rPI1") (pin "51") (pinfunction "GPIO15_51") (pintype "passive"))
    )
    (net (code "37") (name "GPIO16") (class "Default")
      (node (ref "HA") (pin "29") (pinfunction "29_29") (pintype "passive"))
      (node (ref "J16") (pin "36") (pinfunction "GPIO16_36") (pintype "passive"))
      (node (ref "rPI1") (pin "29") (pinfunction "GPIO16_29") (pintype "passive"))
    )
    (net (code "38") (name "GPIO17") (class "Default")
      (node (ref "HA") (pin "50") (pinfunction "50_50") (pintype "passive"))
      (node (ref "J16") (pin "11") (pinfunction "GPIO17_11") (pintype "passive"))
      (node (ref "rPI1") (pin "50") (pinfunction "GPIO17_50") (pintype "passive"))
    )
    (net (code "39") (name "GPIO18") (class "Default")
      (node (ref "HA") (pin "49") (pinfunction "49_49") (pintype "passive"))
      (node (ref "J16") (pin "12") (pinfunction "GPIO18_12") (pintype "passive"))
      (node (ref "rPI1") (pin "49") (pinfunction "GPIO18_49") (pintype "passive"))
    )
    (net (code "40") (name "GPIO19") (class "Default")
      (node (ref "HA") (pin "26") (pinfunction "26_26") (pintype "passive"))
      (node (ref "J16") (pin "35") (pinfunction "GPIO19_35") (pintype "passive"))
      (node (ref "rPI1") (pin "26") (pinfunction "GPIO19_26") (pintype "passive"))
    )
    (net (code "41") (name "GPIO20") (class "Default")
      (node (ref "HA") (pin "27") (pinfunction "27_27") (pintype "passive"))
      (node (ref "J16") (pin "38") (pinfunction "GPIO20_38") (pintype "passive"))
      (node (ref "rPI1") (pin "27") (pinfunction "GPIO20_27") (pintype "passive"))
    )
    (net (code "42") (name "GPIO21") (class "Default")
      (node (ref "HA") (pin "25") (pinfunction "25_25") (pintype "passive"))
      (node (ref "J16") (pin "40") (pinfunction "GPIO21_40") (pintype "passive"))
      (node (ref "rPI1") (pin "25") (pinfunction "GPIO21_25") (pintype "passive"))
    )
    (net (code "43") (name "GPIO22") (class "Default")
      (node (ref "HA") (pin "46") (pinfunction "46_46") (pintype "passive"))
      (node (ref "J16") (pin "15") (pinfunction "GPIO22_15") (pintype "passive"))
      (node (ref "rPI1") (pin "46") (pinfunction "GPIO22_46") (pintype "passive"))
    )
    (net (code "44") (name "GPIO23") (class "Default")
      (node (ref "HA") (pin "47") (pinfunction "47_47") (pintype "passive"))
      (node (ref "J16") (pin "16") (pinfunction "GPIO23_16") (pintype "passive"))
      (node (ref "rPI1") (pin "47") (pinfunction "GPIO23_47") (pintype "passive"))
    )
    (net (code "45") (name "GPIO24") (class "Default")
      (node (ref "HA") (pin "45") (pinfunction "45_45") (pintype "passive"))
      (node (ref "J16") (pin "18") (pinfunction "GPIO24_18") (pintype "passive"))
      (node (ref "rPI1") (pin "45") (pinfunction "GPIO24_45") (pintype "passive"))
    )
    (net (code "46") (name "GPIO25") (class "Default")
      (node (ref "HA") (pin "41") (pinfunction "41_41") (pintype "passive"))
      (node (ref "J16") (pin "22") (pinfunction "GPIO25_22") (pintype "passive"))
      (node (ref "rPI1") (pin "41") (pinfunction "GPIO25_41") (pintype "passive"))
    )
    (net (code "47") (name "GPIO26") (class "Default")
      (node (ref "HA") (pin "24") (pinfunction "24_24") (pintype "passive"))
      (node (ref "J16") (pin "37") (pinfunction "GPIO26_37") (pintype "passive"))
      (node (ref "rPI1") (pin "24") (pinfunction "GPIO26_24") (pintype "passive"))
    )
    (net (code "48") (name "GPIO27") (class "Default")
      (node (ref "HA") (pin "48") (pinfunction "48_48") (pintype "passive"))
      (node (ref "J16") (pin "13") (pinfunction "GPIO27_13") (pintype "passive"))
      (node (ref "rPI1") (pin "48") (pinfunction "GPIO27_48") (pintype "passive"))
    )
    (net (code "49") (name "HDMI0_CEC") (class "Default")
      (node (ref "HB") (pin "51") (pinfunction "51_51") (pintype "passive"))
      (node (ref "rPI1") (pin "151") (pinfunction "HDMI0_CEC_151") (pintype "passive"))
    )
    (net (code "50") (name "HDMI0_CLK_N") (class "Default")
      (node (ref "HB") (pin "90") (pinfunction "90_90") (pintype "passive"))
      (node (ref "rPI1") (pin "190") (pinfunction "HDMI0_CLK_N_190") (pintype "passive"))
    )
    (net (code "51") (name "HDMI0_CLK_P") (class "Default")
      (node (ref "HB") (pin "88") (pinfunction "88_88") (pintype "passive"))
      (node (ref "rPI1") (pin "188") (pinfunction "HDMI0_CLK_P_188") (pintype "passive"))
    )
    (net (code "52") (name "HDMI0_HOTPLUG") (class "Default")
      (node (ref "HB") (pin "53") (pinfunction "53_53") (pintype "passive"))
      (node (ref "rPI1") (pin "153") (pinfunction "HDMI0_HOTPLUG_153") (pintype "passive"))
    )
    (net (code "53") (name "HDMI0_SCL") (class "Default")
      (node (ref "HB") (pin "100") (pinfunction "100_100") (pintype "passive"))
      (node (ref "rPI1") (pin "200") (pinfunction "HDMI0_SCL_200") (pintype "passive"))
    )
    (net (code "54") (name "HDMI0_SDA") (class "Default")
      (node (ref "HB") (pin "99") (pinfunction "99_99") (pintype "passive"))
      (node (ref "rPI1") (pin "199") (pinfunction "HDMI0_SDA_199") (pintype "passive"))
    )
    (net (code "55") (name "HDMI0_TX0_N") (class "Default")
      (node (ref "HB") (pin "84") (pinfunction "84_84") (pintype "passive"))
      (node (ref "rPI1") (pin "184") (pinfunction "HDMI0_TX0_N_184") (pintype "passive"))
    )
    (net (code "56") (name "HDMI0_TX0_P") (class "Default")
      (node (ref "HB") (pin "82") (pinfunction "82_82") (pintype "passive"))
      (node (ref "rPI1") (pin "182") (pinfunction "HDMI0_TX0_P_182") (pintype "passive"))
    )
    (net (code "57") (name "HDMI0_TX1_N") (class "Default")
      (node (ref "HB") (pin "78") (pinfunction "78_78") (pintype "passive"))
      (node (ref "rPI1") (pin "178") (pinfunction "HDMI0_TX1_N_178") (pintype "passive"))
    )
    (net (code "58") (name "HDMI0_TX1_P") (class "Default")
      (node (ref "HB") (pin "76") (pinfunction "76_76") (pintype "passive"))
      (node (ref "rPI1") (pin "176") (pinfunction "HDMI0_TX1_P_176") (pintype "passive"))
    )
    (net (code "59") (name "HDMI0_TX2_N") (class "Default")
      (node (ref "HB") (pin "72") (pinfunction "72_72") (pintype "passive"))
      (node (ref "rPI1") (pin "172") (pinfunction "HDMI0_TX2_N_172") (pintype "passive"))
    )
    (net (code "60") (name "HDMI0_TX2_P") (class "Default")
      (node (ref "HB") (pin "70") (pinfunction "70_70") (pintype "passive"))
      (node (ref "rPI1") (pin "170") (pinfunction "HDMI0_TX2_P_170") (pintype "passive"))
    )
    (net (code "61") (name "HDMI1_CEC") (class "Default")
      (node (ref "HB") (pin "49") (pinfunction "49_49") (pintype "passive"))
      (node (ref "rPI1") (pin "149") (pinfunction "HDMI1_CEC_149") (pintype "passive"))
    )
    (net (code "62") (name "HDMI1_CLK_N") (class "Default")
      (node (ref "HB") (pin "66") (pinfunction "66_66") (pintype "passive"))
      (node (ref "rPI1") (pin "166") (pinfunction "HDMI1_CLK_N_166") (pintype "passive"))
    )
    (net (code "63") (name "HDMI1_CLK_P") (class "Default")
      (node (ref "HB") (pin "64") (pinfunction "64_64") (pintype "passive"))
      (node (ref "rPI1") (pin "164") (pinfunction "HDMI1_CLK_P_164") (pintype "passive"))
    )
    (net (code "64") (name "HDMI1_HOTPLUG") (class "Default")
      (node (ref "HB") (pin "43") (pinfunction "43_43") (pintype "passive"))
      (node (ref "rPI1") (pin "143") (pinfunction "HDMI1_HOTPLUG_143") (pintype "passive"))
    )
    (net (code "65") (name "HDMI1_SCL") (class "Default")
      (node (ref "HB") (pin "47") (pinfunction "47_47") (pintype "passive"))
      (node (ref "rPI1") (pin "147") (pinfunction "HDMI1_SCL_147") (pintype "passive"))
    )
    (net (code "66") (name "HDMI1_SDA") (class "Default")
      (node (ref "HB") (pin "45") (pinfunction "45_45") (pintype "passive"))
      (node (ref "rPI1") (pin "145") (pinfunction "HDMI1_SDA_145") (pintype "passive"))
    )
    (net (code "67") (name "HDMI1_TX0_N") (class "Default")
      (node (ref "HB") (pin "60") (pinfunction "60_60") (pintype "passive"))
      (node (ref "rPI1") (pin "160") (pinfunction "HDMI1_TX0_N_160") (pintype "passive"))
    )
    (net (code "68") (name "HDMI1_TX0_P") (class "Default")
      (node (ref "HB") (pin "58") (pinfunction "58_58") (pintype "passive"))
      (node (ref "rPI1") (pin "158") (pinfunction "HDMI1_TX0_P_158") (pintype "passive"))
    )
    (net (code "69") (name "HDMI1_TX1_N") (class "Default")
      (node (ref "HB") (pin "54") (pinfunction "54_54") (pintype "passive"))
      (node (ref "rPI1") (pin "154") (pinfunction "HDMI1_TX1_N_154") (pintype "passive"))
    )
    (net (code "70") (name "HDMI1_TX1_P") (class "Default")
      (node (ref "HB") (pin "52") (pinfunction "52_52") (pintype "passive"))
      (node (ref "rPI1") (pin "152") (pinfunction "HDMI1_TX1_P_152") (pintype "passive"))
    )
    (net (code "71") (name "HDMI1_TX2_N") (class "Default")
      (node (ref "HB") (pin "48") (pinfunction "48_48") (pintype "passive"))
      (node (ref "rPI1") (pin "148") (pinfunction "HDMI1_TX2_N_148") (pintype "passive"))
    )
    (net (code "72") (name "HDMI1_TX2_P") (class "Default")
      (node (ref "HB") (pin "46") (pinfunction "46_46") (pintype "passive"))
      (node (ref "rPI1") (pin "146") (pinfunction "HDMI1_TX2_P_146") (pintype "passive"))
    )
    (net (code "73") (name "ID_SC") (class "Default")
      (node (ref "HA") (pin "35") (pinfunction "35_35") (pintype "passive"))
      (node (ref "J16") (pin "28") (pinfunction "ID_SC_28") (pintype "passive"))
      (node (ref "rPI1") (pin "35") (pinfunction "ID_SC_35") (pintype "passive"))
    )
    (net (code "74") (name "ID_SD") (class "Default")
      (node (ref "HA") (pin "36") (pinfunction "36_36") (pintype "passive"))
      (node (ref "J16") (pin "27") (pinfunction "ID_SD_27") (pintype "passive"))
      (node (ref "rPI1") (pin "36") (pinfunction "ID_SD_36") (pintype "passive"))
    )
    (net (code "75") (name "Net-(CASE_FAN-Pad2)") (class "Default")
      (node (ref "CASE_FAN") (pin "2") (pinfunction "2_2") (pintype "passive"))
      (node (ref "FB12") (pin "2") (pinfunction "2_2") (pintype "passive"))
    )
    (net (code "76") (name "Net-(CPU_FAN-Pad2)") (class "Default")
      (node (ref "CPU_FAN") (pin "2") (pinfunction "2_2") (pintype "passive"))
      (node (ref "FB11") (pin "2") (pinfunction "2_2") (pintype "passive"))
    )
    (net (code "77") (name "Net-(FB22-Pad2)") (class "Default")
      (node (ref "FB22") (pin "2") (pinfunction "2_2") (pintype "passive"))
      (node (ref "J4") (pin "1") (pinfunction "1_1") (pintype "passive"))
    )
    (net (code "78") (name "Net-(rPI1A-CAM_GPIO1)") (class "Default")
      (node (ref "HA") (pin "100") (pinfunction "100_100") (pintype "passive"))
      (node (ref "rPI1") (pin "100") (pinfunction "CAM_GPIO1_100") (pintype "passive"))
    )
    (net (code "79") (name "Net-(rPI1A-CC1)") (class "Default")
      (node (ref "HA") (pin "94") (pinfunction "94_94") (pintype "passive"))
      (node (ref "rPI1") (pin "94") (pinfunction "CC1_94") (pintype "passive"))
    )
    (net (code "80") (name "Net-(rPI1A-CC2)") (class "Default")
      (node (ref "HA") (pin "96") (pinfunction "96_96") (pintype "passive"))
      (node (ref "rPI1") (pin "96") (pinfunction "CC2_96") (pintype "passive"))
    )
    (net (code "81") (name "Net-(rPI1A-Camera_GPIO)") (class "Default")
      (node (ref "HA") (pin "97") (pinfunction "97_97") (pintype "passive"))
      (node (ref "rPI1") (pin "97") (pinfunction "Camera_GPIO_97") (pintype "passive"))
    )
    (net (code "82") (name "Net-(rPI1A-EEPROM_nWP)") (class "Default")
      (node (ref "HA") (pin "20") (pinfunction "20_20") (pintype "passive"))
      (node (ref "rPI1") (pin "20") (pinfunction "EEPROM_nWP_20") (pintype "passive"))
    )
    (net (code "83") (name "Net-(rPI1A-Ethernet_SYNC_OUT(1.8v))") (class "Default")
      (node (ref "HA") (pin "18") (pinfunction "18_18") (pintype "passive"))
      (node (ref "rPI1") (pin "18") (pinfunction "Ethernet_SYNC_OUT(1.8v)_18") (pintype "passive"))
    )
    (net (code "84") (name "Net-(rPI1A-Global_EN)") (class "Default")
      (node (ref "HA") (pin "99") (pinfunction "99_99") (pintype "passive"))
      (node (ref "rPI1") (pin "99") (pinfunction "Global_EN_99") (pintype "passive"))
    )
    (net (code "85") (name "Net-(rPI1A-Reserved)") (class "Default")
      (node (ref "HA") (pin "76") (pinfunction "76_76") (pintype "passive"))
      (node (ref "rPI1") (pin "76") (pinfunction "Reserved_76") (pintype "passive"))
    )
    (net (code "86") (name "Net-(rPI1A-SCL0)") (class "Default")
      (node (ref "HA") (pin "80") (pinfunction "80_80") (pintype "passive"))
      (node (ref "rPI1") (pin "80") (pinfunction "SCL0_80") (pintype "passive"))
    )
    (net (code "87") (name "Net-(rPI1A-SDA0)") (class "Default")
      (node (ref "HA") (pin "82") (pinfunction "82_82") (pintype "passive"))
      (node (ref "rPI1") (pin "82") (pinfunction "SDA0_82") (pintype "passive"))
    )
    (net (code "88") (name "Net-(rPI1A-SD_DAT4)") (class "Default")
      (node (ref "HA") (pin "68") (pinfunction "68_68") (pintype "passive"))
      (node (ref "rPI1") (pin "68") (pinfunction "SD_DAT4_68") (pintype "passive"))
    )
    (net (code "89") (name "Net-(rPI1A-SD_DAT5)") (class "Default")
      (node (ref "HA") (pin "64") (pinfunction "64_64") (pintype "passive"))
      (node (ref "rPI1") (pin "64") (pinfunction "SD_DAT5_64") (pintype "passive"))
    )
    (net (code "90") (name "Net-(rPI1A-SD_DAT6)") (class "Default")
      (node (ref "HA") (pin "72") (pinfunction "72_72") (pintype "passive"))
      (node (ref "rPI1") (pin "72") (pinfunction "SD_DAT6_72") (pintype "passive"))
    )
    (net (code "91") (name "Net-(rPI1A-SD_DAT7)") (class "Default")
      (node (ref "HA") (pin "70") (pinfunction "70_70") (pintype "passive"))
      (node (ref "rPI1") (pin "70") (pinfunction "SD_DAT7_70") (pintype "passive"))
    )
    (net (code "92") (name "Net-(rPI1A-SD_VDD_Override)") (class "Default")
      (node (ref "HA") (pin "73") (pinfunction "73_73") (pintype "passive"))
      (node (ref "rPI1") (pin "73") (pinfunction "SD_VDD_Override_73") (pintype "passive"))
    )
    (net (code "93") (name "Net-(rPI1A-nPI_LED_PWR)") (class "Default")
      (node (ref "HA") (pin "95") (pinfunction "95_95") (pintype "passive"))
      (node (ref "rPI1") (pin "95") (pinfunction "nPI_LED_PWR_95") (pintype "passive"))
    )
    (net (code "94") (name "Net-(rPI1B-MIPI0_C_N)") (class "Default")
      (node (ref "HB") (pin "27") (pinfunction "27_27") (pintype "passive"))
      (node (ref "rPI1") (pin "127") (pinfunction "MIPI0_C_N_127") (pintype "passive"))
    )
    (net (code "95") (name "Net-(rPI1B-MIPI0_C_P)") (class "Default")
      (node (ref "HB") (pin "29") (pinfunction "29_29") (pintype "passive"))
      (node (ref "rPI1") (pin "129") (pinfunction "MIPI0_C_P_129") (pintype "passive"))
    )
    (net (code "96") (name "Net-(rPI1B-MIPI0_D0_N)") (class "Default")
      (node (ref "HB") (pin "15") (pinfunction "15_15") (pintype "passive"))
      (node (ref "rPI1") (pin "115") (pinfunction "MIPI0_D0_N_115") (pintype "passive"))
    )
    (net (code "97") (name "Net-(rPI1B-MIPI0_D0_P)") (class "Default")
      (node (ref "HB") (pin "17") (pinfunction "17_17") (pintype "passive"))
      (node (ref "rPI1") (pin "117") (pinfunction "MIPI0_D0_P_117") (pintype "passive"))
    )
    (net (code "98") (name "Net-(rPI1B-MIPI0_D1_N)") (class "Default")
      (node (ref "HB") (pin "21") (pinfunction "21_21") (pintype "passive"))
      (node (ref "rPI1") (pin "121") (pinfunction "MIPI0_D1_N_121") (pintype "passive"))
    )
    (net (code "99") (name "Net-(rPI1B-MIPI0_D1_P)") (class "Default")
      (node (ref "HB") (pin "23") (pinfunction "23_23") (pintype "passive"))
      (node (ref "rPI1") (pin "123") (pinfunction "MIPI0_D1_P_123") (pintype "passive"))
    )
    (net (code "100") (name "Net-(rPI1B-MIPI0_D2_N)") (class "Default")
      (node (ref "HB") (pin "33") (pinfunction "33_33") (pintype "passive"))
      (node (ref "rPI1") (pin "133") (pinfunction "MIPI0_D2_N_133") (pintype "passive"))
    )
    (net (code "101") (name "Net-(rPI1B-MIPI0_D2_P)") (class "Default")
      (node (ref "HB") (pin "35") (pinfunction "35_35") (pintype "passive"))
      (node (ref "rPI1") (pin "135") (pinfunction "MIPI0_D2_P_135") (pintype "passive"))
    )
    (net (code "102") (name "Net-(rPI1B-MIPI0_D3_N)") (class "Default")
      (node (ref "HB") (pin "39") (pinfunction "39_39") (pintype "passive"))
      (node (ref "rPI1") (pin "139") (pinfunction "MIPI0_D3_N_139") (pintype "passive"))
    )
    (net (code "103") (name "Net-(rPI1B-MIPI0_D3_P)") (class "Default")
      (node (ref "HB") (pin "41") (pinfunction "41_41") (pintype "passive"))
      (node (ref "rPI1") (pin "141") (pinfunction "MIPI0_D3_P_141") (pintype "passive"))
    )
    (net (code "104") (name "Net-(rPI1B-MIPI1_C_N)") (class "Default")
      (node (ref "HB") (pin "87") (pinfunction "87_87") (pintype "passive"))
      (node (ref "rPI1") (pin "187") (pinfunction "MIPI1_C_N_187") (pintype "passive"))
    )
    (net (code "105") (name "Net-(rPI1B-MIPI1_C_P)") (class "Default")
      (node (ref "HB") (pin "89") (pinfunction "89_89") (pintype "passive"))
      (node (ref "rPI1") (pin "189") (pinfunction "MIPI1_C_P_189") (pintype "passive"))
    )
    (net (code "106") (name "Net-(rPI1B-MIPI1_D0_N)") (class "Default")
      (node (ref "HB") (pin "75") (pinfunction "75_75") (pintype "passive"))
      (node (ref "rPI1") (pin "175") (pinfunction "MIPI1_D0_N_175") (pintype "passive"))
    )
    (net (code "107") (name "Net-(rPI1B-MIPI1_D0_P)") (class "Default")
      (node (ref "HB") (pin "77") (pinfunction "77_77") (pintype "passive"))
      (node (ref "rPI1") (pin "177") (pinfunction "MIPI1_D0_P_177") (pintype "passive"))
    )
    (net (code "108") (name "Net-(rPI1B-MIPI1_D1_N)") (class "Default")
      (node (ref "HB") (pin "81") (pinfunction "81_81") (pintype "passive"))
      (node (ref "rPI1") (pin "181") (pinfunction "MIPI1_D1_N_181") (pintype "passive"))
    )
    (net (code "109") (name "Net-(rPI1B-MIPI1_D1_P)") (class "Default")
      (node (ref "HB") (pin "83") (pinfunction "83_83") (pintype "passive"))
      (node (ref "rPI1") (pin "183") (pinfunction "MIPI1_D1_P_183") (pintype "passive"))
    )
    (net (code "110") (name "Net-(rPI1B-MIPI1_D2_N)") (class "Default")
      (node (ref "HB") (pin "93") (pinfunction "93_93") (pintype "passive"))
      (node (ref "rPI1") (pin "193") (pinfunction "MIPI1_D2_N_193") (pintype "passive"))
    )
    (net (code "111") (name "Net-(rPI1B-MIPI1_D2_P)") (class "Default")
      (node (ref "HB") (pin "95") (pinfunction "95_95") (pintype "passive"))
      (node (ref "rPI1") (pin "195") (pinfunction "MIPI1_D2_P_195") (pintype "passive"))
    )
    (net (code "112") (name "Net-(rPI1B-MIPI1_D3_N)") (class "Default")
      (node (ref "HB") (pin "94") (pinfunction "94_94") (pintype "passive"))
      (node (ref "rPI1") (pin "194") (pinfunction "MIPI1_D3_N_194") (pintype "passive"))
    )
    (net (code "113") (name "Net-(rPI1B-MIPI1_D3_P)") (class "Default")
      (node (ref "HB") (pin "96") (pinfunction "96_96") (pintype "passive"))
      (node (ref "rPI1") (pin "196") (pinfunction "MIPI1_D3_P_196") (pintype "passive"))
    )
    (net (code "114") (name "Net-(rPI1B-PCIE_PWR_EN)") (class "Default")
      (node (ref "HB") (pin "6") (pinfunction "6_6") (pintype "passive"))
      (node (ref "rPI1") (pin "106") (pinfunction "PCIE_PWR_EN_106") (pintype "passive"))
    )
    (net (code "115") (name "Net-(rPI1B-PCIE_nWAKE)") (class "Default")
      (node (ref "HB") (pin "4") (pinfunction "4_4") (pintype "passive"))
      (node (ref "rPI1") (pin "104") (pinfunction "PCIE_nWAKE_104") (pintype "passive"))
    )
    (net (code "116") (name "Net-(rPI1B-VBUS_EN)") (class "Default")
      (node (ref "HB") (pin "11") (pinfunction "11_11") (pintype "passive"))
      (node (ref "rPI1") (pin "111") (pinfunction "VBUS_EN_111") (pintype "passive"))
    )
    (net (code "117") (name "PCIe_CLK_N") (class "Default")
      (node (ref "HB") (pin "12") (pinfunction "12_12") (pintype "passive"))
      (node (ref "J10") (pin "A14") (pinfunction "A14_A14") (pintype "passive"))
      (node (ref "rPI1") (pin "112") (pinfunction "PCIe_CLK_N_112") (pintype "passive"))
    )
    (net (code "118") (name "PCIe_CLK_P") (class "Default")
      (node (ref "HB") (pin "10") (pinfunction "10_10") (pintype "passive"))
      (node (ref "J10") (pin "A13") (pinfunction "A13_A13") (pintype "passive"))
      (node (ref "rPI1") (pin "110") (pinfunction "PCIe_CLK_P_110") (pintype "passive"))
    )
    (net (code "119") (name "PCIe_CLK_nREQ") (class "Default")
      (node (ref "HB") (pin "2") (pinfunction "2_2") (pintype "passive"))
      (node (ref "J10") (pin "B12") (pinfunction "B12_B12") (pintype "passive"))
      (node (ref "rPI1") (pin "102") (pinfunction "PCIe_CLK_nREQ_102") (pintype "passive"))
    )
    (net (code "120") (name "PCIe_RX_N") (class "Default")
      (node (ref "HB") (pin "18") (pinfunction "18_18") (pintype "passive"))
      (node (ref "J10") (pin "A17") (pinfunction "A17_A17") (pintype "passive"))
      (node (ref "rPI1") (pin "118") (pinfunction "PCIe_RX_N_118") (pintype "passive"))
    )
    (net (code "121") (name "PCIe_RX_P") (class "Default")
      (node (ref "HB") (pin "16") (pinfunction "16_16") (pintype "passive"))
      (node (ref "J10") (pin "A16") (pinfunction "A16_A16") (pintype "passive"))
      (node (ref "rPI1") (pin "116") (pinfunction "PCIe_RX_P_116") (pintype "passive"))
    )
    (net (code "122") (name "PCIe_TX_N") (class "Default")
      (node (ref "HB") (pin "24") (pinfunction "24_24") (pintype "passive"))
      (node (ref "J10") (pin "B15") (pinfunction "B15_B15") (pintype "passive"))
      (node (ref "rPI1") (pin "124") (pinfunction "PCIe_TX_N_124") (pintype "passive"))
    )
    (net (code "123") (name "PCIe_TX_P") (class "Default")
      (node (ref "HB") (pin "22") (pinfunction "22_22") (pintype "passive"))
      (node (ref "J10") (pin "B14") (pinfunction "B14_B14") (pintype "passive"))
      (node (ref "rPI1") (pin "122") (pinfunction "PCIe_TX_P_122") (pintype "passive"))
    )
    (net (code "124") (name "PCIe_nRST") (class "Default")
      (node (ref "HB") (pin "9") (pinfunction "9_9") (pintype "passive"))
      (node (ref "J10") (pin "A11") (pinfunction "A11_A11") (pintype "passive"))
      (node (ref "rPI1") (pin "109") (pinfunction "PCIe_nRST_109") (pintype "passive"))
    )
    (net (code "125") (name "PW_BUT") (class "Default")
      (node (ref "HA") (pin "92") (pinfunction "92_92") (pintype "passive"))
      (node (ref "HDR1") (pin "10") (pinfunction "10_10") (pintype "passive"))
      (node (ref "rPI1") (pin "92") (pinfunction "RUN_PG_92") (pintype "passive"))
    )
    (net (code "126") (name "SD_CLK") (class "Default")
      (node (ref "HA") (pin "57") (pinfunction "57_57") (pintype "passive"))
      (node (ref "rPI1") (pin "57") (pinfunction "SD_CLK_57") (pintype "passive"))
    )
    (net (code "127") (name "SD_CMD") (class "Default")
      (node (ref "HA") (pin "62") (pinfunction "62_62") (pintype "passive"))
      (node (ref "rPI1") (pin "62") (pinfunction "SD_CMD_62") (pintype "passive"))
    )
    (net (code "128") (name "SD_DAT0") (class "Default")
      (node (ref "HA") (pin "63") (pinfunction "63_63") (pintype "passive"))
      (node (ref "rPI1") (pin "63") (pinfunction "SD_DAT0_63") (pintype "passive"))
    )
    (net (code "129") (name "SD_DAT1") (class "Default")
      (node (ref "HA") (pin "67") (pinfunction "67_67") (pintype "passive"))
      (node (ref "rPI1") (pin "67") (pinfunction "SD_DAT1_67") (pintype "passive"))
    )
    (net (code "130") (name "SD_DAT2") (class "Default")
      (node (ref "HA") (pin "69") (pinfunction "69_69") (pintype "passive"))
      (node (ref "rPI1") (pin "69") (pinfunction "SD_DAT2_69") (pintype "passive"))
    )
    (net (code "131") (name "SD_DAT3") (class "Default")
      (node (ref "HA") (pin "61") (pinfunction "61_61") (pintype "passive"))
      (node (ref "rPI1") (pin "61") (pinfunction "SD_DAT3_61") (pintype "passive"))
    )
    (net (code "132") (name "SD_PWR_ON") (class "Default")
      (node (ref "HA") (pin "75") (pinfunction "75_75") (pintype "passive"))
      (node (ref "rPI1") (pin "75") (pinfunction "SD_PWR_ON_75") (pintype "passive"))
    )
    (net (code "133") (name "USB2_UP_N") (class "Default")
      (node (ref "HB") (pin "3") (pinfunction "3_3") (pintype "passive"))
      (node (ref "rPI1") (pin "103") (pinfunction "USB2_N_103") (pintype "passive"))
    )
    (net (code "134") (name "USB2_UP_OTG") (class "Default")
      (node (ref "HB") (pin "1") (pinfunction "1_1") (pintype "passive"))
      (node (ref "rPI1") (pin "101") (pinfunction "USB_OTG_ID_101") (pintype "passive"))
    )
    (net (code "135") (name "USB2_UP_P") (class "Default")
      (node (ref "HB") (pin "5") (pinfunction "5_5") (pintype "passive"))
      (node (ref "rPI1") (pin "105") (pinfunction "USB2_P_105") (pintype "passive"))
    )
    (net (code "136") (name "USB3-0-D_N") (class "Default")
      (node (ref "HB") (pin "36") (pinfunction "36_36") (pintype "passive"))
      (node (ref "rPI1") (pin "136") (pinfunction "USB3-0-D_N_136") (pintype "passive"))
    )
    (net (code "137") (name "USB3-0-D_P") (class "Default")
      (node (ref "HB") (pin "34") (pinfunction "34_34") (pintype "passive"))
      (node (ref "rPI1") (pin "134") (pinfunction "USB3-0-D_P_134") (pintype "passive"))
    )
    (net (code "138") (name "USB3-0-RX_N") (class "Default")
      (node (ref "HB") (pin "28") (pinfunction "28_28") (pintype "passive"))
      (node (ref "rPI1") (pin "128") (pinfunction "USB3-0-RX_N_128") (pintype "passive"))
    )
    (net (code "139") (name "USB3-0-RX_P") (class "Default")
      (node (ref "HB") (pin "30") (pinfunction "30_30") (pintype "passive"))
      (node (ref "rPI1") (pin "130") (pinfunction "USB3-0-RX_P_130") (pintype "passive"))
    )
    (net (code "140") (name "USB3-0-TX_N") (class "Default")
      (node (ref "HB") (pin "40") (pinfunction "40_40") (pintype "passive"))
      (node (ref "rPI1") (pin "140") (pinfunction "USB3-0-TX_N_140") (pintype "passive"))
    )
    (net (code "141") (name "USB3-0-TX_P") (class "Default")
      (node (ref "HB") (pin "42") (pinfunction "42_42") (pintype "passive"))
      (node (ref "rPI1") (pin "142") (pinfunction "USB3-0-TX_P_142") (pintype "passive"))
    )
    (net (code "142") (name "USB3-1-D_N") (class "Default")
      (node (ref "HB") (pin "65") (pinfunction "65_65") (pintype "passive"))
      (node (ref "rPI1") (pin "165") (pinfunction "USB3-1-D_N_165") (pintype "passive"))
    )
    (net (code "143") (name "USB3-1-D_P") (class "Default")
      (node (ref "HB") (pin "63") (pinfunction "63_63") (pintype "passive"))
      (node (ref "rPI1") (pin "163") (pinfunction "USB3-1-D_P_163") (pintype "passive"))
    )
    (net (code "144") (name "USB3-1-RX_N") (class "Default")
      (node (ref "HB") (pin "57") (pinfunction "57_57") (pintype "passive"))
      (node (ref "rPI1") (pin "157") (pinfunction "USB3-1-RX_N_157") (pintype "passive"))
    )
    (net (code "145") (name "USB3-1-RX_P") (class "Default")
      (node (ref "HB") (pin "59") (pinfunction "59_59") (pintype "passive"))
      (node (ref "rPI1") (pin "159") (pinfunction "USB3-1-RX_P_159") (pintype "passive"))
    )
    (net (code "146") (name "USB3-1-TX_N") (class "Default")
      (node (ref "HB") (pin "69") (pinfunction "69_69") (pintype "passive"))
      (node (ref "rPI1") (pin "169") (pinfunction "USB3-1-TX_N_169") (pintype "passive"))
    )
    (net (code "147") (name "USB3-1-TX_P") (class "Default")
      (node (ref "HB") (pin "71") (pinfunction "71_71") (pintype "passive"))
      (node (ref "rPI1") (pin "171") (pinfunction "USB3-1-TX_P_171") (pintype "passive"))
    )
    (net (code "148") (name "Wifi") (class "Default")
      (node (ref "HA") (pin "89") (pinfunction "89_89") (pintype "passive"))
      (node (ref "HDR1") (pin "2") (pinfunction "2_2") (pintype "passive"))
      (node (ref "rPI1") (pin "89") (pinfunction "WiFi_nDisable_89") (pintype "passive"))
    )
    (net (code "149") (name "nRPI") (class "Default")
      (node (ref "HA") (pin "93") (pinfunction "93_93") (pintype "passive"))
      (node (ref "HDR1") (pin "8") (pinfunction "8_8") (pintype "passive"))
      (node (ref "rPI1") (pin "93") (pinfunction "nRPIBOOT_93") (pintype "passive"))
    )
    (net (code "150") (name "unconnected-(CASE_FAN-Pad3)") (class "Default")
      (node (ref "CASE_FAN") (pin "3") (pinfunction "3_3") (pintype "passive"))
    )
    (net (code "151") (name "unconnected-(CASE_FAN-Pad4)") (class "Default")
      (node (ref "CASE_FAN") (pin "4") (pinfunction "4_4") (pintype "passive"))
    )
    (net (code "152") (name "unconnected-(HDR1-Pad6)") (class "Default")
      (node (ref "HDR1") (pin "6") (pinfunction "6_6") (pintype "passive"))
    )
    (net (code "153") (name "unconnected-(J10-PadA1)") (class "Default")
      (node (ref "J10") (pin "A1") (pinfunction "A1_A1") (pintype "passive"))
    )
    (net (code "154") (name "unconnected-(J10-PadA7)") (class "Default")
      (node (ref "J10") (pin "A7") (pinfunction "A7_A7") (pintype "passive"))
    )
    (net (code "155") (name "unconnected-(J10-PadA19)") (class "Default")
      (node (ref "J10") (pin "A19") (pinfunction "A19_A19") (pintype "passive"))
    )
    (net (code "156") (name "unconnected-(J10-PadA20)") (class "Default")
      (node (ref "J10") (pin "A20") (pinfunction "A20_A20") (pintype "passive"))
    )
    (net (code "157") (name "unconnected-(J10-PadA21)") (class "Default")
      (node (ref "J10") (pin "A21") (pinfunction "A21_A21") (pintype "passive"))
    )
    (net (code "158") (name "unconnected-(J10-PadA22)") (class "Default")
      (node (ref "J10") (pin "A22") (pinfunction "A22_A22") (pintype "passive"))
    )
    (net (code "159") (name "unconnected-(J10-PadA23)") (class "Default")
      (node (ref "J10") (pin "A23") (pinfunction "A23_A23") (pintype "passive"))
    )
    (net (code "160") (name "unconnected-(J10-PadA24)") (class "Default")
      (node (ref "J10") (pin "A24") (pinfunction "A24_A24") (pintype "passive"))
    )
    (net (code "161") (name "unconnected-(J10-PadA25)") (class "Default")
      (node (ref "J10") (pin "A25") (pinfunction "A25_A25") (pintype "passive"))
    )
    (net (code "162") (name "unconnected-(J10-PadA26)") (class "Default")
      (node (ref "J10") (pin "A26") (pinfunction "A26_A26") (pintype "passive"))
    )
    (net (code "163") (name "unconnected-(J10-PadA27)") (class "Default")
      (node (ref "J10") (pin "A27") (pinfunction "A27_A27") (pintype "passive"))
    )
    (net (code "164") (name "unconnected-(J10-PadA28)") (class "Default")
      (node (ref "J10") (pin "A28") (pinfunction "A28_A28") (pintype "passive"))
    )
    (net (code "165") (name "unconnected-(J10-PadA29)") (class "Default")
      (node (ref "J10") (pin "A29") (pinfunction "A29_A29") (pintype "passive"))
    )
    (net (code "166") (name "unconnected-(J10-PadA30)") (class "Default")
      (node (ref "J10") (pin "A30") (pinfunction "A30_A30") (pintype "passive"))
    )
    (net (code "167") (name "unconnected-(J10-PadA31)") (class "Default")
      (node (ref "J10") (pin "A31") (pinfunction "A31_A31") (pintype "passive"))
    )
    (net (code "168") (name "unconnected-(J10-PadA32)") (class "Default")
      (node (ref "J10") (pin "A32") (pinfunction "A32_A32") (pintype "passive"))
    )
    (net (code "169") (name "unconnected-(J10-PadA33)") (class "Default")
      (node (ref "J10") (pin "A33") (pinfunction "A33_A33") (pintype "passive"))
    )
    (net (code "170") (name "unconnected-(J10-PadA34)") (class "Default")
      (node (ref "J10") (pin "A34") (pinfunction "A34_A34") (pintype "passive"))
    )
    (net (code "171") (name "unconnected-(J10-PadA35)") (class "Default")
      (node (ref "J10") (pin "A35") (pinfunction "A35_A35") (pintype "passive"))
    )
    (net (code "172") (name "unconnected-(J10-PadA36)") (class "Default")
      (node (ref "J10") (pin "A36") (pinfunction "A36_A36") (pintype "passive"))
    )
    (net (code "173") (name "unconnected-(J10-PadA37)") (class "Default")
      (node (ref "J10") (pin "A37") (pinfunction "A37_A37") (pintype "passive"))
    )
    (net (code "174") (name "unconnected-(J10-PadA38)") (class "Default")
      (node (ref "J10") (pin "A38") (pinfunction "A38_A38") (pintype "passive"))
    )
    (net (code "175") (name "unconnected-(J10-PadA39)") (class "Default")
      (node (ref "J10") (pin "A39") (pinfunction "A39_A39") (pintype "passive"))
    )
    (net (code "176") (name "unconnected-(J10-PadA40)") (class "Default")
      (node (ref "J10") (pin "A40") (pinfunction "A40_A40") (pintype "passive"))
    )
    (net (code "177") (name "unconnected-(J10-PadB5)") (class "Default")
      (node (ref "J10") (pin "B5") (pinfunction "B5_B5") (pintype "passive"))
    )
    (net (code "178") (name "unconnected-(J10-PadB6)") (class "Default")
      (node (ref "J10") (pin "B6") (pinfunction "B6_B6") (pintype "passive"))
    )
    (net (code "179") (name "unconnected-(J10-PadB11)") (class "Default")
      (node (ref "J10") (pin "B11") (pinfunction "B11_B11") (pintype "passive"))
    )
    (net (code "180") (name "unconnected-(J10-PadB17)") (class "Default")
      (node (ref "J10") (pin "B17") (pinfunction "B17_B17") (pintype "passive"))
    )
    (net (code "181") (name "unconnected-(J10-PadB19)") (class "Default")
      (node (ref "J10") (pin "B19") (pinfunction "B19_B19") (pintype "passive"))
    )
    (net (code "182") (name "unconnected-(J10-PadB20)") (class "Default")
      (node (ref "J10") (pin "B20") (pinfunction "B20_B20") (pintype "passive"))
    )
    (net (code "183") (name "unconnected-(J10-PadB21)") (class "Default")
      (node (ref "J10") (pin "B21") (pinfunction "B21_B21") (pintype "passive"))
    )
    (net (code "184") (name "unconnected-(J10-PadB22)") (class "Default")
      (node (ref "J10") (pin "B22") (pinfunction "B22_B22") (pintype "passive"))
    )
    (net (code "185") (name "unconnected-(J10-PadB23)") (class "Default")
      (node (ref "J10") (pin "B23") (pinfunction "B23_B23") (pintype "passive"))
    )
    (net (code "186") (name "unconnected-(J10-PadB24)") (class "Default")
      (node (ref "J10") (pin "B24") (pinfunction "B24_B24") (pintype "passive"))
    )
    (net (code "187") (name "unconnected-(J10-PadB25)") (class "Default")
      (node (ref "J10") (pin "B25") (pinfunction "B25_B25") (pintype "passive"))
    )
    (net (code "188") (name "unconnected-(J10-PadB26)") (class "Default")
      (node (ref "J10") (pin "B26") (pinfunction "B26_B26") (pintype "passive"))
    )
    (net (code "189") (name "unconnected-(J10-PadB27)") (class "Default")
      (node (ref "J10") (pin "B27") (pinfunction "B27_B27") (pintype "passive"))
    )
    (net (code "190") (name "unconnected-(J10-PadB28)") (class "Default")
      (node (ref "J10") (pin "B28") (pinfunction "B28_B28") (pintype "passive"))
    )
    (net (code "191") (name "unconnected-(J10-PadB29)") (class "Default")
      (node (ref "J10") (pin "B29") (pinfunction "B29_B29") (pintype "passive"))
    )
    (net (code "192") (name "unconnected-(J10-PadB30)") (class "Default")
      (node (ref "J10") (pin "B30") (pinfunction "B30_B30") (pintype "passive"))
    )
    (net (code "193") (name "unconnected-(J10-PadB31)") (class "Default")
      (node (ref "J10") (pin "B31") (pinfunction "B31_B31") (pintype "passive"))
    )
    (net (code "194") (name "unconnected-(J10-PadB32)") (class "Default")
      (node (ref "J10") (pin "B32") (pinfunction "B32_B32") (pintype "passive"))
    )
    (net (code "195") (name "unconnected-(J10-PadB33)") (class "Default")
      (node (ref "J10") (pin "B33") (pinfunction "B33_B33") (pintype "passive"))
    )
    (net (code "196") (name "unconnected-(J10-PadB34)") (class "Default")
      (node (ref "J10") (pin "B34") (pinfunction "B34_B34") (pintype "passive"))
    )
    (net (code "197") (name "unconnected-(J10-PadB35)") (class "Default")
      (node (ref "J10") (pin "B35") (pinfunction "B35_B35") (pintype "passive"))
    )
    (net (code "198") (name "unconnected-(J10-PadB36)") (class "Default")
      (node (ref "J10") (pin "B36") (pinfunction "B36_B36") (pintype "passive"))
    )
    (net (code "199") (name "unconnected-(J10-PadB37)") (class "Default")
      (node (ref "J10") (pin "B37") (pinfunction "B37_B37") (pintype "passive"))
    )
    (net (code "200") (name "unconnected-(J10-PadB38)") (class "Default")
      (node (ref "J10") (pin "B38") (pinfunction "B38_B38") (pintype "passive"))
    )
    (net (code "201") (name "unconnected-(J10-PadB39)") (class "Default")
      (node (ref "J10") (pin "B39") (pinfunction "B39_B39") (pintype "passive"))
    )
    (net (code "202") (name "unconnected-(J10-PadB40)") (class "Default")
      (node (ref "J10") (pin "B40") (pinfunction "B40_B40") (pintype "passive"))
    )
  )
)
